# sender.net
KiCad netlist of a schematic drawn in EAGLE
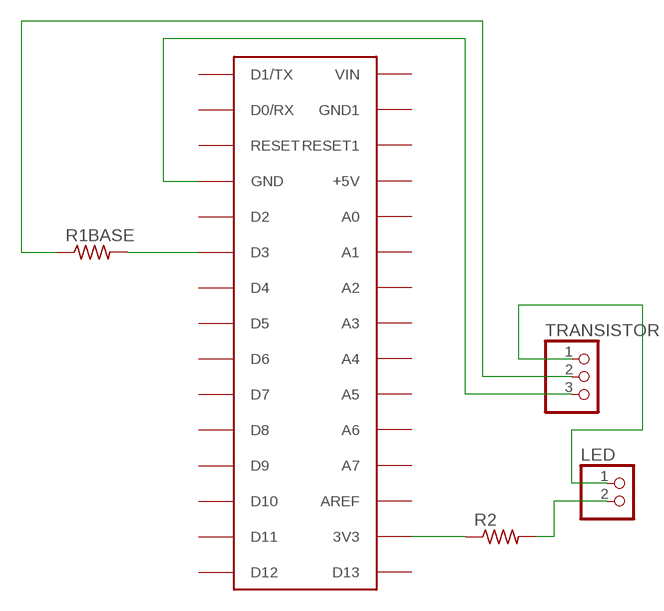
[diagram p0: schematic, sheet 1]

(export (version "E")
  (design (tool "Eeschema 10.0.6"))
  (components
    (comp (ref "LED")
      (value "PINHD-1X2")
      (footprint "eagle-import:1X02")
      (libsource (lib "eagle-import") (part "PINHD-1X2"))
    )
    (comp (ref "R1BASE")
      (value "R-US_0207/12")
      (footprint "eagle-import:0207_12")
      (libsource (lib "eagle-import") (part "R-US_0207/12"))
    )
    (comp (ref "R2")
      (value "R-US_0207/12")
      (footprint "eagle-import:0207_12")
      (libsource (lib "eagle-import") (part "R-US_0207/12"))
    )
    (comp (ref "TRANSISTOR")
      (value "PINHD-1X3")
      (footprint "eagle-import:1X03")
      (libsource (lib "eagle-import") (part "PINHD-1X3"))
    )
    (comp (ref "U$1")
      (value "ARDUINONANO")
      (footprint "eagle-import:PDIP-32")
      (libsource (lib "eagle-import") (part "ARDUINONANO"))
    )
  )
  (nets
    (net (code "1") (name "Net-(LED-Pad1)") (class "Default")
      (node (ref "LED") (pin "1") (pinfunction "1_1") (pintype "passive"))
      (node (ref "TRANSISTOR") (pin "1") (pinfunction "1_1") (pintype "passive"))
    )
    (net (code "2") (name "Net-(LED-Pad2)") (class "Default")
      (node (ref "LED") (pin "2") (pinfunction "2_2") (pintype "passive"))
      (node (ref "R2") (pin "2") (pinfunction "2_2") (pintype "passive"))
    )
    (net (code "3") (name "Net-(R1BASE-Pad1)") (class "Default")
      (node (ref "R1BASE") (pin "1") (pinfunction "1_1") (pintype "passive"))
      (node (ref "TRANSISTOR") (pin "2") (pinfunction "2_2") (pintype "passive"))
    )
    (net (code "4") (name "Net-(R1BASE-Pad2)") (class "Default")
      (node (ref "R1BASE") (pin "2") (pinfunction "2_2") (pintype "passive"))
      (node (ref "U$1") (pin "D3") (pinfunction "D3_D3") (pintype "bidirectional"))
    )
    (net (code "5") (name "Net-(R2-Pad1)") (class "Default")
      (node (ref "R2") (pin "1") (pinfunction "1_1") (pintype "passive"))
      (node (ref "U$1") (pin "3V3") (pinfunction "3V3_3V3") (pintype "bidirectional"))
    )
    (net (code "6") (name "Net-(TRANSISTOR-Pad3)") (class "Default")
      (node (ref "TRANSISTOR") (pin "3") (pinfunction "3_3") (pintype "passive"))
      (node (ref "U$1") (pin "GND") (pinfunction "GND_GND") (pintype "bidirectional"))
    )
    (net (code "7") (name "unconnected-(U$1-Pad+5V)") (class "Default")
      (node (ref "U$1") (pin "+5V") (pinfunction "+5V_+5V") (pintype "bidirectional"))
    )
    (net (code "8") (name "unconnected-(U$1-PadA0)") (class "Default")
      (node (ref "U$1") (pin "A0") (pinfunction "A0_A0") (pintype "bidirectional"))
    )
    (net (code "9") (name "unconnected-(U$1-PadA1)") (class "Default")
      (node (ref "U$1") (pin "A1") (pinfunction "A1_A1") (pintype "bidirectional"))
    )
    (net (code "10") (name "unconnected-(U$1-PadA2)") (class "Default")
      (node (ref "U$1") (pin "A2") (pinfunction "A2_A2") (pintype "bidirectional"))
    )
    (net (code "11") (name "unconnected-(U$1-PadA3)") (class "Default")
      (node (ref "U$1") (pin "A3") (pinfunction "A3_A3") (pintype "bidirectional"))
    )
    (net (code "12") (name "unconnected-(U$1-PadA4)") (class "Default")
      (node (ref "U$1") (pin "A4") (pinfunction "A4_A4") (pintype "bidirectional"))
    )
    (net (code "13") (name "unconnected-(U$1-PadA5)") (class "Default")
      (node (ref "U$1") (pin "A5") (pinfunction "A5_A5") (pintype "bidirectional"))
    )
    (net (code "14") (name "unconnected-(U$1-PadA6)") (class "Default")
      (node (ref "U$1") (pin "A6") (pinfunction "A6_A6") (pintype "bidirectional"))
    )
    (net (code "15") (name "unconnected-(U$1-PadA7)") (class "Default")
      (node (ref "U$1") (pin "A7") (pinfunction "A7_A7") (pintype "bidirectional"))
    )
    (net (code "16") (name "unconnected-(U$1-PadAREF)") (class "Default")
      (node (ref "U$1") (pin "AREF") (pinfunction "AREF_AREF") (pintype "bidirectional"))
    )
    (net (code "17") (name "unconnected-(U$1-PadD0{slash}RX)") (class "Default")
      (node (ref "U$1") (pin "D0/RX") (pinfunction "D0/RX_D0/RX") (pintype "bidirectional"))
    )
    (net (code "18") (name "unconnected-(U$1-PadD1{slash}TX)") (class "Default")
      (node (ref "U$1") (pin "D1/TX") (pinfunction "D1/TX_D1/TX") (pintype "bidirectional"))
    )
    (net (code "19") (name "unconnected-(U$1-PadD2)") (class "Default")
      (node (ref "U$1") (pin "D2") (pinfunction "D2_D2") (pintype "bidirectional"))
    )
    (net (code "20") (name "unconnected-(U$1-PadD4)") (class "Default")
      (node (ref "U$1") (pin "D4") (pinfunction "D4_D4") (pintype "bidirectional"))
    )
    (net (code "21") (name "unconnected-(U$1-PadD5)") (class "Default")
      (node (ref "U$1") (pin "D5") (pinfunction "D5_D5") (pintype "bidirectional"))
    )
    (net (code "22") (name "unconnected-(U$1-PadD6)") (class "Default")
      (node (ref "U$1") (pin "D6") (pinfunction "D6_D6") (pintype "bidirectional"))
    )
    (net (code "23") (name "unconnected-(U$1-PadD7)") (class "Default")
      (node (ref "U$1") (pin "D7") (pinfunction "D7_D7") (pintype "bidirectional"))
    )
    (net (code "24") (name "unconnected-(U$1-PadD8)") (class "Default")
      (node (ref "U$1") (pin "D8") (pinfunction "D8_D8") (pintype "bidirectional"))
    )
    (net (code "25") (name "unconnected-(U$1-PadD9)") (class "Default")
      (node (ref "U$1") (pin "D9") (pinfunction "D9_D9") (pintype "bidirectional"))
    )
    (net (code "26") (name "unconnected-(U$1-PadD10)") (class "Default")
      (node (ref "U$1") (pin "D10") (pinfunction "D10_D10") (pintype "bidirectional"))
    )
    (net (code "27") (name "unconnected-(U$1-PadD11)") (class "Default")
      (node (ref "U$1") (pin "D11") (pinfunction "D11_D11") (pintype "bidirectional"))
    )
    (net (code "28") (name "unconnected-(U$1-PadD12)") (class "Default")
      (node (ref "U$1") (pin "D12") (pinfunction "D12_D12") (pintype "bidirectional"))
    )
    (net (code "29") (name "unconnected-(U$1-PadD13)") (class "Default")
      (node (ref "U$1") (pin "D13") (pinfunction "D13_D13") (pintype "bidirectional"))
    )
    (net (code "30") (name "unconnected-(U$1-PadGND1)") (class "Default")
      (node (ref "U$1") (pin "GND1") (pinfunction "GND1_GND1") (pintype "bidirectional"))
    )
    (net (code "31") (name "unconnected-(U$1-PadRESET)") (class "Default")
      (node (ref "U$1") (pin "RESET") (pinfunction "RESET_RESET") (pintype "bidirectional"))
    )
    (net (code "32") (name "unconnected-(U$1-PadRESET1)") (class "Default")
      (node (ref "U$1") (pin "RESET1") (pinfunction "RESET1_RESET1") (pintype "bidirectional"))
    )
    (net (code "33") (name "unconnected-(U$1-PadVIN)") (class "Default")
      (node (ref "U$1") (pin "VIN") (pinfunction "VIN_VIN") (pintype "bidirectional"))
    )
  )
)
